# I2C-Oled-Backpack-Newhaven.net
KiCad netlist of a schematic drawn in EAGLE
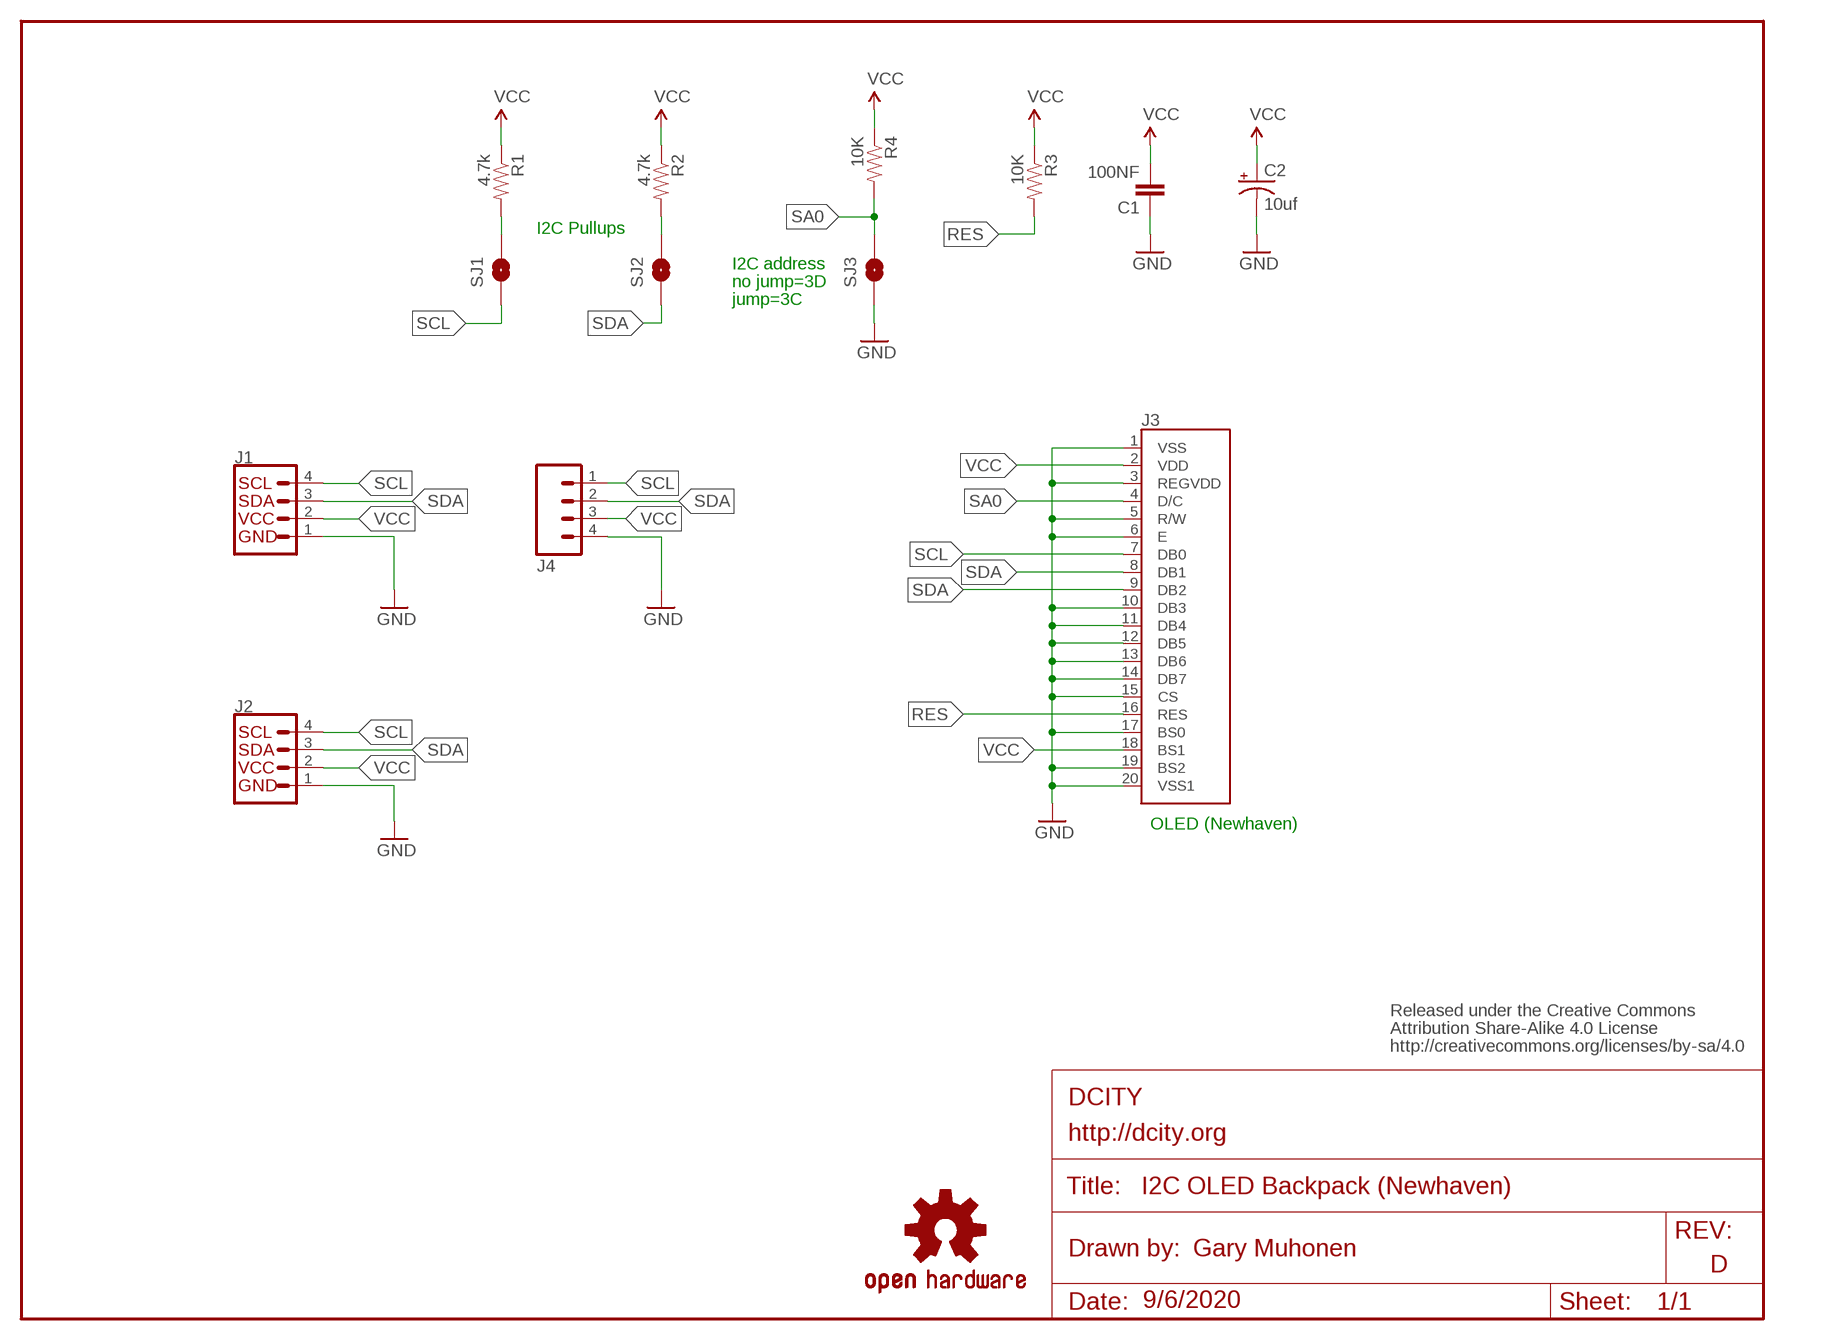
[diagram p0: schematic, sheet 1]

(export (version "E")
  (design (tool "Eeschema 10.0.6"))
  (components
    (comp (ref "C1")
      (value "100NF")
      (footprint "eagle-import:0805-CAP")
      (libsource (lib "eagle-import") (part "CAP0805"))
    )
    (comp (ref "C2")
      (value "10uf")
      (footprint "eagle-import:0805-POL")
      (libsource (lib "eagle-import") (part "CAP_POL0805"))
    )
    (comp (ref "J1")
      (value "QWIIC_RIGHT_ANGLE")
      (footprint "eagle-import:JST04_1MM_RA")
      (libsource (lib "eagle-import") (part "QWIIC_CONNECTORJS-1MM"))
    )
    (comp (ref "J2")
      (value "QWIIC_RIGHT_ANGLE")
      (footprint "eagle-import:JST04_1MM_RA")
      (libsource (lib "eagle-import") (part "QWIIC_CONNECTORJS-1MM"))
    )
    (comp (ref "J3")
      (value "LCD-NEWHAVEN-LOCK")
      (footprint "eagle-import:1X20_LOCK")
      (libsource (lib "eagle-import") (part "LCD-NEWHAVEN-LOCK"))
    )
    (comp (ref "J4")
      (value "M04LOCK")
      (footprint "eagle-import:1X04_LOCK")
      (libsource (lib "eagle-import") (part "M04LOCK"))
    )
    (comp (ref "LOGO1")
      (value "OSHW-LOGOS")
      (footprint "eagle-import:OSHW-LOGO-S")
      (libsource (lib "eagle-import") (part "OSHW-LOGOS"))
    )
    (comp (ref "R1")
      (value "4.7k")
      (footprint "eagle-import:0805-RES")
      (libsource (lib "eagle-import") (part "RESISTOR0805"))
    )
    (comp (ref "R2")
      (value "4.7k")
      (footprint "eagle-import:0805-RES")
      (libsource (lib "eagle-import") (part "RESISTOR0805"))
    )
    (comp (ref "R3")
      (value "10K")
      (footprint "eagle-import:0805-RES")
      (libsource (lib "eagle-import") (part "RESISTOR0805"))
    )
    (comp (ref "R4")
      (value "10K")
      (footprint "eagle-import:0805-RES")
      (libsource (lib "eagle-import") (part "RESISTOR0805"))
    )
    (comp (ref "SJ1")
      (value "SOLDERJUMPERNC")
      (footprint "eagle-import:SJ_2S")
      (libsource (lib "eagle-import") (part "SOLDERJUMPERNC"))
    )
    (comp (ref "SJ2")
      (value "SOLDERJUMPERNC")
      (footprint "eagle-import:SJ_2S")
      (libsource (lib "eagle-import") (part "SOLDERJUMPERNC"))
    )
    (comp (ref "SJ3")
      (value "SOLDERJUMPERNC")
      (footprint "eagle-import:SJ_2S")
      (libsource (lib "eagle-import") (part "SOLDERJUMPERNC"))
    )
    (comp (ref "U$2")
      (value "CREATIVE_COMMONS")
      (footprint "eagle-import:CREATIVE_COMMONS")
      (libsource (lib "eagle-import") (part "CREATIVE_COMMONS"))
    )
  )
  (nets
    (net (code "1") (name "GND") (class "Default")
      (node (ref "C1") (pin "1") (pinfunction "1_1") (pintype "passive"))
      (node (ref "C2") (pin "-") (pinfunction "-_-") (pintype "passive"))
      (node (ref "J1") (pin "1") (pinfunction "1_1") (pintype "power_in"))
      (node (ref "J2") (pin "1") (pinfunction "1_1") (pintype "power_in"))
      (node (ref "J3") (pin "1") (pinfunction "VSS_1") (pintype "bidirectional"))
      (node (ref "J3") (pin "10") (pinfunction "DB3_10") (pintype "bidirectional"))
      (node (ref "J3") (pin "11") (pinfunction "DB4_11") (pintype "bidirectional"))
      (node (ref "J3") (pin "12") (pinfunction "DB5_12") (pintype "bidirectional"))
      (node (ref "J3") (pin "13") (pinfunction "DB6_13") (pintype "bidirectional"))
      (node (ref "J3") (pin "14") (pinfunction "DB7_14") (pintype "bidirectional"))
      (node (ref "J3") (pin "15") (pinfunction "CS_15") (pintype "bidirectional"))
      (node (ref "J3") (pin "17") (pinfunction "BS0_17") (pintype "bidirectional"))
      (node (ref "J3") (pin "19") (pinfunction "BS2_19") (pintype "bidirectional"))
      (node (ref "J3") (pin "20") (pinfunction "VSS1_20") (pintype "bidirectional"))
      (node (ref "J3") (pin "3") (pinfunction "REGVDD_3") (pintype "bidirectional"))
      (node (ref "J3") (pin "5") (pinfunction "R/W_5") (pintype "input"))
      (node (ref "J3") (pin "6") (pinfunction "E_6") (pintype "input"))
      (node (ref "J4") (pin "4") (pinfunction "4_4") (pintype "passive"))
      (node (ref "SJ3") (pin "1") (pinfunction "1_1") (pintype "passive"))
    )
    (net (code "2") (name "Net-(R1-Pad2)") (class "Default")
      (node (ref "R1") (pin "2") (pinfunction "2_2") (pintype "passive"))
      (node (ref "SJ1") (pin "2") (pinfunction "2_2") (pintype "passive"))
    )
    (net (code "3") (name "Net-(R2-Pad2)") (class "Default")
      (node (ref "R2") (pin "2") (pinfunction "2_2") (pintype "passive"))
      (node (ref "SJ2") (pin "2") (pinfunction "2_2") (pintype "passive"))
    )
    (net (code "4") (name "RES") (class "Default")
      (node (ref "J3") (pin "16") (pinfunction "RES_16") (pintype "bidirectional"))
      (node (ref "R3") (pin "2") (pinfunction "2_2") (pintype "passive"))
    )
    (net (code "5") (name "SA0") (class "Default")
      (node (ref "J3") (pin "4") (pinfunction "D/C_4") (pintype "input"))
      (node (ref "R4") (pin "2") (pinfunction "2_2") (pintype "passive"))
      (node (ref "SJ3") (pin "2") (pinfunction "2_2") (pintype "passive"))
    )
    (net (code "6") (name "SCL") (class "Default")
      (node (ref "J1") (pin "4") (pinfunction "4_4") (pintype "passive"))
      (node (ref "J2") (pin "4") (pinfunction "4_4") (pintype "passive"))
      (node (ref "J3") (pin "7") (pinfunction "DB0_7") (pintype "bidirectional"))
      (node (ref "J4") (pin "1") (pinfunction "1_1") (pintype "passive"))
      (node (ref "SJ1") (pin "1") (pinfunction "1_1") (pintype "passive"))
    )
    (net (code "7") (name "SDA") (class "Default")
      (node (ref "J1") (pin "3") (pinfunction "3_3") (pintype "passive"))
      (node (ref "J2") (pin "3") (pinfunction "3_3") (pintype "passive"))
      (node (ref "J3") (pin "8") (pinfunction "DB1_8") (pintype "bidirectional"))
      (node (ref "J3") (pin "9") (pinfunction "DB2_9") (pintype "bidirectional"))
      (node (ref "J4") (pin "2") (pinfunction "2_2") (pintype "passive"))
      (node (ref "SJ2") (pin "1") (pinfunction "1_1") (pintype "passive"))
    )
    (net (code "8") (name "VCC") (class "Default")
      (node (ref "C1") (pin "2") (pinfunction "2_2") (pintype "passive"))
      (node (ref "C2") (pin "+") (pinfunction "+_+") (pintype "passive"))
      (node (ref "J1") (pin "2") (pinfunction "2_2") (pintype "power_in"))
      (node (ref "J2") (pin "2") (pinfunction "2_2") (pintype "power_in"))
      (node (ref "J3") (pin "18") (pinfunction "BS1_18") (pintype "bidirectional"))
      (node (ref "J3") (pin "2") (pinfunction "VDD_2") (pintype "open_collector"))
      (node (ref "J4") (pin "3") (pinfunction "3_3") (pintype "passive"))
      (node (ref "R1") (pin "1") (pinfunction "1_1") (pintype "passive"))
      (node (ref "R2") (pin "1") (pinfunction "1_1") (pintype "passive"))
      (node (ref "R3") (pin "1") (pinfunction "1_1") (pintype "passive"))
      (node (ref "R4") (pin "1") (pinfunction "1_1") (pintype "passive"))
    )
  )
)
